# 10_-_RFID.net
KiCad netlist of a schematic drawn in Altium Designer
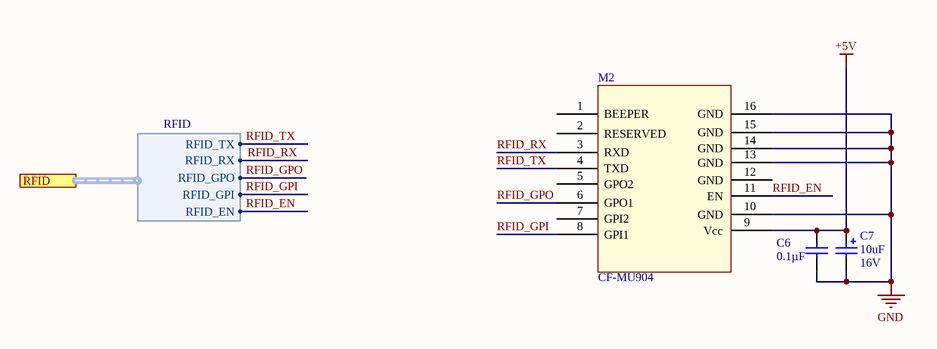
[diagram p0: [10] - RFID.SchDoc]

(export (version "E")
  (design (tool "Eeschema 10.0.6"))
  (components
    (comp (ref "C6")
      (value "Capacitor")
      (footprint "0603_C")
      (description "Chip Capacitor Nonpolar")
      (fields
        (field (name "MANUFACTURER") "Kemet")
        (field (name "MANUFACTURER PART NUMBER") "C0603C104K5RACTU")
        (field (name "CAPACITANCE") "0.1µF")
      )
      (libsource (lib "Altium_Library") (part "Capacitor"))
    )
    (comp (ref "C7")
      (value "Capacitor Polarized")
      (footprint "Blue Tractor-2021:Tantalum 3216 A")
      (description "CAP TANT 10UF 10% 16V 1206")
      (fields
        (field (name "MANUFACTURER") "Vishay Sprague")
        (field (name "MANUFACTURER PART NUMBER") "293D106X9016A2TE3")
        (field (name "CAPACITANCE") "10uF")
        (field (name "VOLTAGE RATING") "16V")
      )
      (libsource (lib "Altium_Library") (part "Capacitor Polarized"))
    )
    (comp (ref "M2")
      (value "CF-MU904")
      (footprint "Blue Tractor-2021:CF-MU904")
      (libsource (lib "Blue Tractor-2021") (part "CF-MU904"))
    )
  )
  (nets
    (net (code "2") (name "+5V") (class "Default")
      (node (ref "C6") (pin "2") (pinfunction "2_2") (pintype "passive"))
      (node (ref "C7") (pin "1") (pinfunction "1_1") (pintype "passive"))
      (node (ref "M2") (pin "9") (pinfunction "Vcc_9") (pintype "power_in"))
    )
    (net (code "3") (name "/RFID_EN") (class "Default")
      (node (ref "M2") (pin "11") (pinfunction "EN_11") (pintype "power_in"))
    )
    (net (code "4") (name "/RFID_GPI") (class "Default")
      (node (ref "M2") (pin "8") (pinfunction "GPI1_8") (pintype "passive"))
    )
    (net (code "5") (name "/RFID_GPO") (class "Default")
      (node (ref "M2") (pin "6") (pinfunction "GPO1_6") (pintype "passive"))
    )
    (net (code "6") (name "/RFID_RX") (class "Default")
      (node (ref "M2") (pin "3") (pinfunction "RXD_3") (pintype "passive"))
    )
    (net (code "7") (name "/RFID_TX") (class "Default")
      (node (ref "M2") (pin "4") (pinfunction "TXD_4") (pintype "passive"))
    )
    (net (code "9") (name "GND") (class "Default")
      (node (ref "C6") (pin "1") (pinfunction "1_1") (pintype "passive"))
      (node (ref "C7") (pin "2") (pinfunction "2_2") (pintype "passive"))
      (node (ref "M2") (pin "10") (pinfunction "GND_10") (pintype "power_in"))
      (node (ref "M2") (pin "13") (pinfunction "GND_13") (pintype "power_in"))
      (node (ref "M2") (pin "14") (pinfunction "GND_14") (pintype "power_in"))
      (node (ref "M2") (pin "15") (pinfunction "GND_15") (pintype "power_in"))
      (node (ref "M2") (pin "16") (pinfunction "GND_16") (pintype "power_in"))
    )
    (net (code "10") (name "unconnected-(M2-BEEPER-Pad1)") (class "Default")
      (node (ref "M2") (pin "1") (pinfunction "BEEPER_1") (pintype "power_in"))
    )
    (net (code "11") (name "unconnected-(M2-GND-Pad12)") (class "Default")
      (node (ref "M2") (pin "12") (pinfunction "GND_12") (pintype "power_in"))
    )
    (net (code "12") (name "unconnected-(M2-GPI2-Pad7)") (class "Default")
      (node (ref "M2") (pin "7") (pinfunction "GPI2_7") (pintype "passive"))
    )
    (net (code "13") (name "unconnected-(M2-GPO2-Pad5)") (class "Default")
      (node (ref "M2") (pin "5") (pinfunction "GPO2_5") (pintype "passive"))
    )
    (net (code "14") (name "unconnected-(M2-RESERVED-Pad2)") (class "Default")
      (node (ref "M2") (pin "2") (pinfunction "RESERVED_2") (pintype "passive"))
    )
  )
)
